# design.net
KiCad netlist of a schematic drawn in Altium Designer
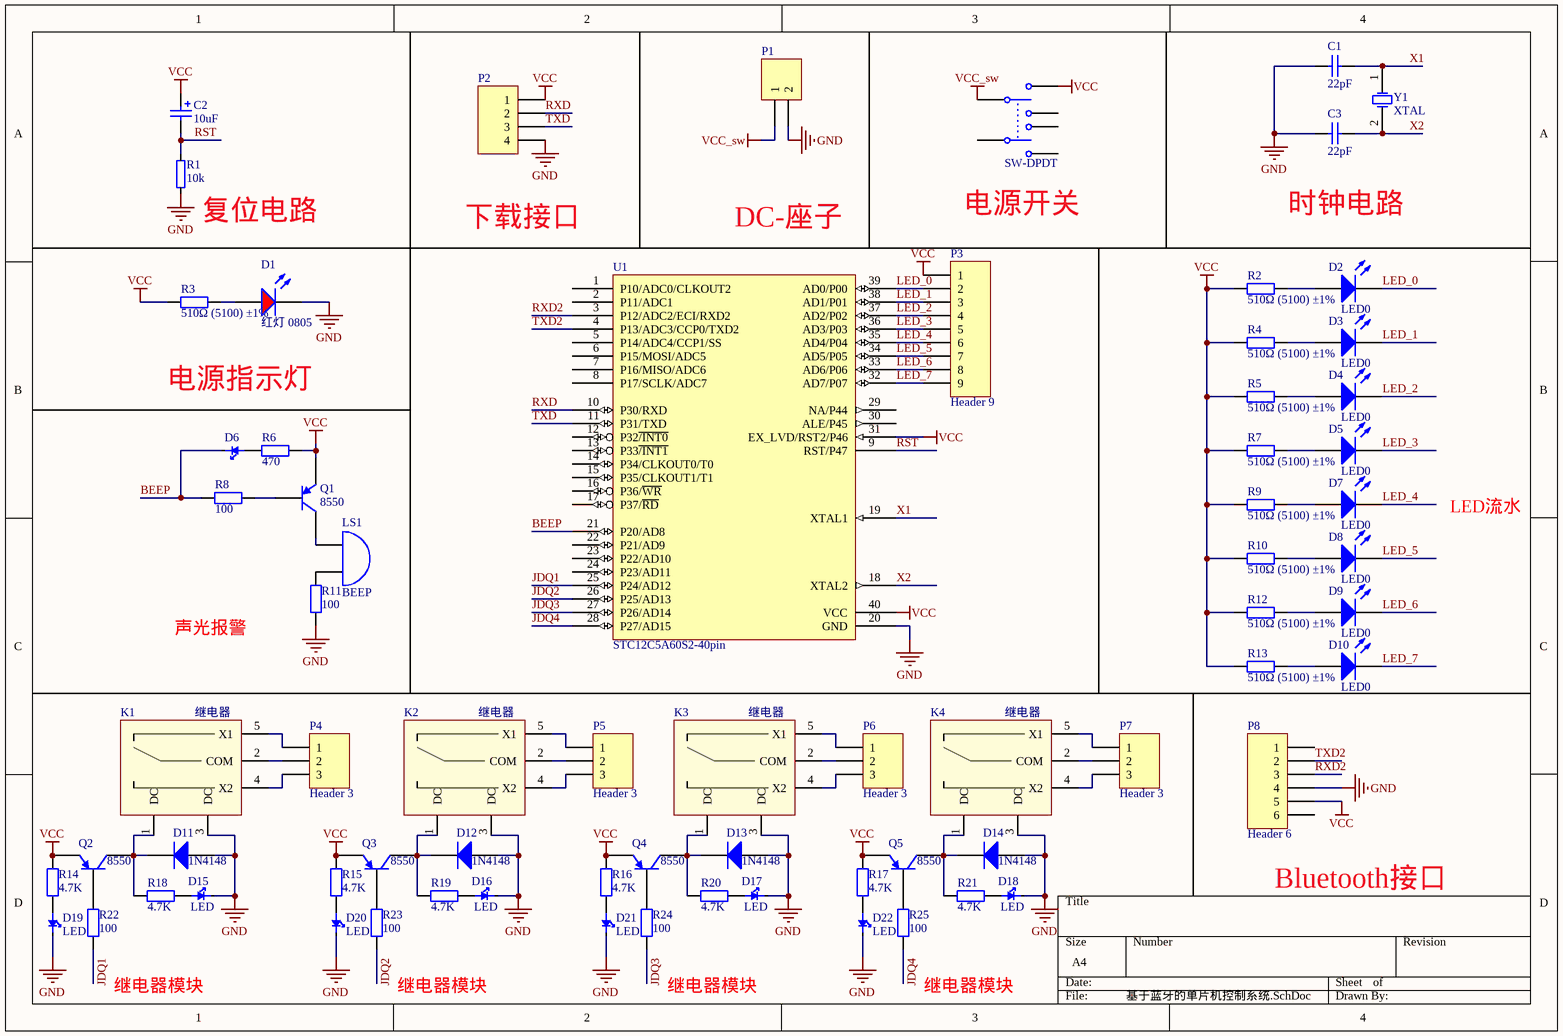
[diagram p0: 基于蓝牙的单片机控制系统.SchDoc]

(export (version "E")
  (design (tool "Eeschema 10.0.6"))
  (components
    (comp (ref "C1")
      (value "22pF")
      (footprint "0805")
      (description "Capacitor")
      (fields (field (name "Comment") "Cap") (field (name "PUBLISHER") "Altium Limited"))
      (libsource (lib "Miscellaneous Devices") (part "Cap"))
    )
    (comp (ref "C2")
      (value "10uF")
      (footprint "RB.2/.5mm")
      (description "Polarized Capacitor (Axial)")
      (fields (field (name "PUBLISHER") "Altium Limited"))
      (libsource (lib "Miscellaneous Devices") (part "Cap Pol2"))
    )
    (comp (ref "C3")
      (value "22pF")
      (footprint "0805")
      (description "Capacitor")
      (fields (field (name "Comment") "Cap") (field (name "PUBLISHER") "Altium Limited"))
      (libsource (lib "Miscellaneous Devices") (part "Cap"))
    )
    (comp (ref "D1")
      (value "红灯 0805")
      (footprint "LC-0805_LED_S1")
      (description "发光二极管")
      (libsource (lib "Miscellaneous Devices LC") (part "0805 红灯"))
    )
    (comp (ref "D2")
      (value "LED0")
      (footprint "HDR1X2")
      (description "Typical INFRARED GaAs LED")
      (fields (field (name "PUBLISHER") "Altium Limited"))
      (libsource (lib "Miscellaneous Devices") (part "LED0"))
    )
    (comp (ref "D3")
      (value "LED0")
      (footprint "HDR1X2")
      (description "Typical INFRARED GaAs LED")
      (fields (field (name "PUBLISHER") "Altium Limited"))
      (libsource (lib "Miscellaneous Devices") (part "LED0"))
    )
    (comp (ref "D4")
      (value "LED0")
      (footprint "HDR1X2")
      (description "Typical INFRARED GaAs LED")
      (fields (field (name "PUBLISHER") "Altium Limited"))
      (libsource (lib "Miscellaneous Devices") (part "LED0"))
    )
    (comp (ref "D5")
      (value "LED0")
      (footprint "HDR1X2")
      (description "Typical INFRARED GaAs LED")
      (fields (field (name "PUBLISHER") "Altium Limited"))
      (libsource (lib "Miscellaneous Devices") (part "LED0"))
    )
    (comp (ref "D6") (value "W") (footprint "LC-0805_LED_S1") (libsource (lib "个人") (part "LED")))
    (comp (ref "D7")
      (value "LED0")
      (footprint "HDR1X2")
      (description "Typical INFRARED GaAs LED")
      (fields (field (name "PUBLISHER") "Altium Limited"))
      (libsource (lib "Miscellaneous Devices") (part "LED0"))
    )
    (comp (ref "D8")
      (value "LED0")
      (footprint "HDR1X2")
      (description "Typical INFRARED GaAs LED")
      (fields (field (name "PUBLISHER") "Altium Limited"))
      (libsource (lib "Miscellaneous Devices") (part "LED0"))
    )
    (comp (ref "D9")
      (value "LED0")
      (footprint "HDR1X2")
      (description "Typical INFRARED GaAs LED")
      (fields (field (name "PUBLISHER") "Altium Limited"))
      (libsource (lib "Miscellaneous Devices") (part "LED0"))
    )
    (comp (ref "D10")
      (value "LED0")
      (footprint "HDR1X2")
      (description "Typical INFRARED GaAs LED")
      (fields (field (name "PUBLISHER") "Altium Limited"))
      (libsource (lib "Miscellaneous Devices") (part "LED0"))
    )
    (comp (ref "D11")
      (value "1N4148")
      (footprint "SMA(DO-214AC)_S5")
      (description "High Conductance Fast Diode")
      (fields (field (name "PUBLISHER") "Altium Limited"))
      (libsource (lib "Miscellaneous Devices") (part "Diode 1N4148"))
    )
    (comp (ref "D12")
      (value "1N4148")
      (footprint "SMA(DO-214AC)_S5")
      (description "High Conductance Fast Diode")
      (fields (field (name "PUBLISHER") "Altium Limited"))
      (libsource (lib "Miscellaneous Devices") (part "Diode 1N4148"))
    )
    (comp (ref "D13")
      (value "1N4148")
      (footprint "SMA(DO-214AC)_S5")
      (description "High Conductance Fast Diode")
      (fields (field (name "PUBLISHER") "Altium Limited"))
      (libsource (lib "Miscellaneous Devices") (part "Diode 1N4148"))
    )
    (comp (ref "D14")
      (value "1N4148")
      (footprint "SMA(DO-214AC)_S5")
      (description "High Conductance Fast Diode")
      (fields (field (name "PUBLISHER") "Altium Limited"))
      (libsource (lib "Miscellaneous Devices") (part "Diode 1N4148"))
    )
    (comp (ref "D15") (value "LED") (footprint "LC-0805_LED_S1") (libsource (lib "个人") (part "LED")))
    (comp (ref "D16") (value "LED") (footprint "LC-0805_LED_S1") (libsource (lib "个人") (part "LED")))
    (comp (ref "D17") (value "LED") (footprint "LC-0805_LED_S1") (libsource (lib "个人") (part "LED")))
    (comp (ref "D18") (value "LED") (footprint "LC-0805_LED_S1") (libsource (lib "个人") (part "LED")))
    (comp (ref "D19") (value "LED") (footprint "LC-0805_LED_S1") (libsource (lib "个人") (part "LED")))
    (comp (ref "D20") (value "LED") (footprint "LC-0805_LED_S1") (libsource (lib "个人") (part "LED")))
    (comp (ref "D21") (value "LED") (footprint "LC-0805_LED_S1") (libsource (lib "个人") (part "LED")))
    (comp (ref "D22") (value "LED") (footprint "LC-0805_LED_S1") (libsource (lib "个人") (part "LED")))
    (comp (ref "K1") (value "继电器") (footprint "继电器5PIN_切换") (libsource (lib "个人") (part "松乐继电器5V-5PIN")))
    (comp (ref "K2") (value "继电器") (footprint "继电器5PIN_切换") (libsource (lib "个人") (part "松乐继电器5V-5PIN")))
    (comp (ref "K3") (value "继电器") (footprint "继电器5PIN_切换") (libsource (lib "个人") (part "松乐继电器5V-5PIN")))
    (comp (ref "K4") (value "继电器") (footprint "继电器5PIN_切换") (libsource (lib "个人") (part "松乐继电器5V-5PIN")))
    (comp (ref "LS1")
      (value "BEEP")
      (footprint "PIN2")
      (description "Electrical Bell")
      (fields (field (name "PUBLISHER") "Altium Limited"))
      (libsource (lib "Miscellaneous Devices") (part "Bell"))
    )
    (comp (ref "P1")
      (value "电源")
      (footprint "DC插座")
      (description "Header, 2-Pin")
      (fields (field (name "PUBLISHER") "Altium Limited"))
      (libsource (lib "Miscellaneous Connectors") (part "Header 2"))
    )
    (comp (ref "P2")
      (value "下载口")
      (footprint "HDR1X4")
      (description "Header, 4-Pin")
      (fields (field (name "PUBLISHER") "Altium Limited"))
      (libsource (lib "Miscellaneous Connectors") (part "Header 4"))
    )
    (comp (ref "P3")
      (value "Header 9")
      (footprint "HDR1X9")
      (description "Header, 9-Pin")
      (fields (field (name "PUBLISHER") "Altium Limited"))
      (libsource (lib "Miscellaneous Connectors") (part "Header 9"))
    )
    (comp (ref "P4")
      (value "Header 3")
      (footprint "KF128-5_3")
      (description "Header, 3-Pin")
      (fields (field (name "PUBLISHER") "Altium Limited"))
      (libsource (lib "Miscellaneous Connectors") (part "Header 3"))
    )
    (comp (ref "P5")
      (value "Header 3")
      (footprint "KF128-5_3")
      (description "Header, 3-Pin")
      (fields (field (name "PUBLISHER") "Altium Limited"))
      (libsource (lib "Miscellaneous Connectors") (part "Header 3"))
    )
    (comp (ref "P6")
      (value "Header 3")
      (footprint "KF128-5_3")
      (description "Header, 3-Pin")
      (fields (field (name "PUBLISHER") "Altium Limited"))
      (libsource (lib "Miscellaneous Connectors") (part "Header 3"))
    )
    (comp (ref "P7")
      (value "Header 3")
      (footprint "KF128-5_3")
      (description "Header, 3-Pin")
      (fields (field (name "PUBLISHER") "Altium Limited"))
      (libsource (lib "Miscellaneous Connectors") (part "Header 3"))
    )
    (comp (ref "P8")
      (value "Header 6")
      (footprint "HDR1X6")
      (description "Header, 6-Pin")
      (fields (field (name "PUBLISHER") "Altium Limited"))
      (libsource (lib "Miscellaneous Connectors") (part "Header 6"))
    )
    (comp (ref "Q1")
      (value "8550")
      (footprint "SOT-23 MOS")
      (description "PNP General Purpose Amplifier")
      (fields (field (name "PUBLISHER") "Altium Limited"))
      (libsource (lib "Miscellaneous Devices") (part "2N3906"))
    )
    (comp (ref "Q2")
      (value "8550")
      (footprint "SOT-23 MOS")
      (description "PNP General Purpose Amplifier")
      (fields (field (name "PUBLISHER") "Altium Limited"))
      (libsource (lib "Miscellaneous Devices") (part "2N3906"))
    )
    (comp (ref "Q3")
      (value "8550")
      (footprint "SOT-23 MOS")
      (description "PNP General Purpose Amplifier")
      (fields (field (name "PUBLISHER") "Altium Limited"))
      (libsource (lib "Miscellaneous Devices") (part "2N3906"))
    )
    (comp (ref "Q4")
      (value "8550")
      (footprint "SOT-23 MOS")
      (description "PNP General Purpose Amplifier")
      (fields (field (name "PUBLISHER") "Altium Limited"))
      (libsource (lib "Miscellaneous Devices") (part "2N3906"))
    )
    (comp (ref "Q5")
      (value "8550")
      (footprint "SOT-23 MOS")
      (description "PNP General Purpose Amplifier")
      (fields (field (name "PUBLISHER") "Altium Limited"))
      (libsource (lib "Miscellaneous Devices") (part "2N3906"))
    )
    (comp (ref "R1") (value "10k") (footprint "0805") (libsource (lib "SCHS") (part "RES5")))
    (comp (ref "R2")
      (value "510Ω (5100) ±1%")
      (footprint "LC-0805_R")
      (description "贴片电阻")
      (libsource (lib "Miscellaneous Devices LC") (part "0805 510Ω (5100) 1%"))
    )
    (comp (ref "R3")
      (value "510Ω (5100) ±1%")
      (footprint "LC-0805_R")
      (description "贴片电阻")
      (libsource (lib "Miscellaneous Devices LC") (part "0805 510Ω (5100) 1%"))
    )
    (comp (ref "R4")
      (value "510Ω (5100) ±1%")
      (footprint "LC-0805_R")
      (description "贴片电阻")
      (libsource (lib "Miscellaneous Devices LC") (part "0805 510Ω (5100) 1%"))
    )
    (comp (ref "R5")
      (value "510Ω (5100) ±1%")
      (footprint "LC-0805_R")
      (description "贴片电阻")
      (libsource (lib "Miscellaneous Devices LC") (part "0805 510Ω (5100) 1%"))
    )
    (comp (ref "R6")
      (value "470")
      (footprint "0805")
      (description "Resistor")
      (fields (field (name "Comment") "Res2") (field (name "PUBLISHER") "Altium Limited"))
      (libsource (lib "") (part "Res2_2"))
    )
    (comp (ref "R7")
      (value "510Ω (5100) ±1%")
      (footprint "LC-0805_R")
      (description "贴片电阻")
      (libsource (lib "Miscellaneous Devices LC") (part "0805 510Ω (5100) 1%"))
    )
    (comp (ref "R8")
      (value "100")
      (footprint "0805")
      (description "Resistor")
      (fields (field (name "Comment") "Res2") (field (name "PUBLISHER") "Altium Limited"))
      (libsource (lib "") (part "Res2_2"))
    )
    (comp (ref "R9")
      (value "510Ω (5100) ±1%")
      (footprint "LC-0805_R")
      (description "贴片电阻")
      (libsource (lib "Miscellaneous Devices LC") (part "0805 510Ω (5100) 1%"))
    )
    (comp (ref "R10")
      (value "510Ω (5100) ±1%")
      (footprint "LC-0805_R")
      (description "贴片电阻")
      (libsource (lib "Miscellaneous Devices LC") (part "0805 510Ω (5100) 1%"))
    )
    (comp (ref "R11")
      (value "100")
      (footprint "0805")
      (description "Resistor")
      (fields (field (name "Comment") "Res2") (field (name "PUBLISHER") "Altium Limited"))
      (libsource (lib "Miscellaneous Devices") (part "Res2"))
    )
    (comp (ref "R12")
      (value "510Ω (5100) ±1%")
      (footprint "LC-0805_R")
      (description "贴片电阻")
      (libsource (lib "Miscellaneous Devices LC") (part "0805 510Ω (5100) 1%"))
    )
    (comp (ref "R13")
      (value "510Ω (5100) ±1%")
      (footprint "LC-0805_R")
      (description "贴片电阻")
      (libsource (lib "Miscellaneous Devices LC") (part "0805 510Ω (5100) 1%"))
    )
    (comp (ref "R14")
      (value "4.7K")
      (footprint "0805")
      (description "Resistor")
      (fields (field (name "PUBLISHER") "Altium Limited"))
      (libsource (lib "") (part "Res2_2"))
    )
    (comp (ref "R15")
      (value "4.7K")
      (footprint "0805")
      (description "Resistor")
      (fields (field (name "PUBLISHER") "Altium Limited"))
      (libsource (lib "") (part "Res2_2"))
    )
    (comp (ref "R16")
      (value "4.7K")
      (footprint "0805")
      (description "Resistor")
      (fields (field (name "PUBLISHER") "Altium Limited"))
      (libsource (lib "") (part "Res2_2"))
    )
    (comp (ref "R17")
      (value "4.7K")
      (footprint "0805")
      (description "Resistor")
      (fields (field (name "PUBLISHER") "Altium Limited"))
      (libsource (lib "") (part "Res2_2"))
    )
    (comp (ref "R18")
      (value "4.7K")
      (footprint "0805")
      (description "Resistor")
      (fields (field (name "PUBLISHER") "Altium Limited"))
      (libsource (lib "") (part "Res2_1"))
    )
    (comp (ref "R19")
      (value "4.7K")
      (footprint "0805")
      (description "Resistor")
      (fields (field (name "PUBLISHER") "Altium Limited"))
      (libsource (lib "") (part "Res2_1"))
    )
    (comp (ref "R20")
      (value "4.7K")
      (footprint "0805")
      (description "Resistor")
      (fields (field (name "PUBLISHER") "Altium Limited"))
      (libsource (lib "") (part "Res2_1"))
    )
    (comp (ref "R21")
      (value "4.7K")
      (footprint "0805")
      (description "Resistor")
      (fields (field (name "PUBLISHER") "Altium Limited"))
      (libsource (lib "") (part "Res2_1"))
    )
    (comp (ref "R22")
      (value "100")
      (footprint "0805")
      (description "Resistor")
      (fields (field (name "PUBLISHER") "Altium Limited"))
      (libsource (lib "Miscellaneous Devices") (part "Res2"))
    )
    (comp (ref "R23")
      (value "100")
      (footprint "0805")
      (description "Resistor")
      (fields (field (name "PUBLISHER") "Altium Limited"))
      (libsource (lib "Miscellaneous Devices") (part "Res2"))
    )
    (comp (ref "R24")
      (value "100")
      (footprint "0805")
      (description "Resistor")
      (fields (field (name "PUBLISHER") "Altium Limited"))
      (libsource (lib "Miscellaneous Devices") (part "Res2"))
    )
    (comp (ref "R25")
      (value "100")
      (footprint "0805")
      (description "Resistor")
      (fields (field (name "PUBLISHER") "Altium Limited"))
      (libsource (lib "Miscellaneous Devices") (part "Res2"))
    )
    (comp (ref "U1")
      (value "STC12C5A60S2-40pin")
      (footprint "DIP40")
      (libsource (lib "个人") (part "STC12C5A60S2-40pin"))
    )
    (comp (ref "Y1")
      (value "XTAL")
      (footprint "XTAL")
      (description "Crystal Oscillator")
      (fields (field (name "PUBLISHER") "Altium Limited"))
      (libsource (lib "Miscellaneous Devices") (part "XTAL"))
    )
    (comp (ref "常按开关1")
      (value "SW-DPDT")
      (footprint "DPDT-6")
      (description "Double-Pole, Double-Throw Switch")
      (fields (field (name "PUBLISHER") "Altium Limited"))
      (libsource (lib "Miscellaneous Devices") (part "SW-DPDT"))
    )
  )
  (nets
    (net (code "1") (name "/BEEP") (class "Default")
      (node (ref "D6") (pin "K") (pinfunction "K_K") (pintype "passive"))
      (node (ref "R8") (pin "2") (pinfunction "2_2") (pintype "passive"))
      (node (ref "U1") (pin "21") (pinfunction "P20/AD8_21") (pintype "bidirectional"))
    )
    (net (code "2") (name "/JDQ1") (class "Default")
      (node (ref "R22") (pin "1") (pinfunction "1_1") (pintype "passive"))
      (node (ref "U1") (pin "25") (pinfunction "P24/AD12_25") (pintype "bidirectional"))
    )
    (net (code "3") (name "/JDQ2") (class "Default")
      (node (ref "R23") (pin "1") (pinfunction "1_1") (pintype "passive"))
      (node (ref "U1") (pin "26") (pinfunction "P25/AD13_26") (pintype "bidirectional"))
    )
    (net (code "4") (name "/JDQ3") (class "Default")
      (node (ref "R24") (pin "1") (pinfunction "1_1") (pintype "passive"))
      (node (ref "U1") (pin "27") (pinfunction "P26/AD14_27") (pintype "bidirectional"))
    )
    (net (code "5") (name "/JDQ4") (class "Default")
      (node (ref "R25") (pin "1") (pinfunction "1_1") (pintype "passive"))
      (node (ref "U1") (pin "28") (pinfunction "P27/AD15_28") (pintype "bidirectional"))
    )
    (net (code "6") (name "/LED_0") (class "Default")
      (node (ref "D2") (pin "2") (pinfunction "K_2") (pintype "passive"))
      (node (ref "P3") (pin "2") (pinfunction "2_2") (pintype "passive"))
      (node (ref "U1") (pin "39") (pinfunction "AD0/P00_39") (pintype "bidirectional"))
    )
    (net (code "7") (name "/LED_1") (class "Default")
      (node (ref "D3") (pin "2") (pinfunction "K_2") (pintype "passive"))
      (node (ref "P3") (pin "3") (pinfunction "3_3") (pintype "passive"))
      (node (ref "U1") (pin "38") (pinfunction "AD1/P01_38") (pintype "bidirectional"))
    )
    (net (code "8") (name "/LED_2") (class "Default")
      (node (ref "D4") (pin "2") (pinfunction "K_2") (pintype "passive"))
      (node (ref "P3") (pin "4") (pinfunction "4_4") (pintype "passive"))
      (node (ref "U1") (pin "37") (pinfunction "AD2/P02_37") (pintype "bidirectional"))
    )
    (net (code "9") (name "/LED_3") (class "Default")
      (node (ref "D5") (pin "2") (pinfunction "K_2") (pintype "passive"))
      (node (ref "P3") (pin "5") (pinfunction "5_5") (pintype "passive"))
      (node (ref "U1") (pin "36") (pinfunction "AD3/P03_36") (pintype "bidirectional"))
    )
    (net (code "10") (name "/LED_4") (class "Default")
      (node (ref "D7") (pin "2") (pinfunction "K_2") (pintype "passive"))
      (node (ref "P3") (pin "6") (pinfunction "6_6") (pintype "passive"))
      (node (ref "U1") (pin "35") (pinfunction "AD4/P04_35") (pintype "bidirectional"))
    )
    (net (code "11") (name "/LED_5") (class "Default")
      (node (ref "D8") (pin "2") (pinfunction "K_2") (pintype "passive"))
      (node (ref "P3") (pin "7") (pinfunction "7_7") (pintype "passive"))
      (node (ref "U1") (pin "34") (pinfunction "AD5/P05_34") (pintype "bidirectional"))
    )
    (net (code "12") (name "/LED_6") (class "Default")
      (node (ref "D9") (pin "2") (pinfunction "K_2") (pintype "passive"))
      (node (ref "P3") (pin "8") (pinfunction "8_8") (pintype "passive"))
      (node (ref "U1") (pin "33") (pinfunction "AD6/P06_33") (pintype "bidirectional"))
    )
    (net (code "13") (name "/LED_7") (class "Default")
      (node (ref "D10") (pin "2") (pinfunction "K_2") (pintype "passive"))
      (node (ref "P3") (pin "9") (pinfunction "9_9") (pintype "passive"))
      (node (ref "U1") (pin "32") (pinfunction "AD7/P07_32") (pintype "bidirectional"))
    )
    (net (code "14") (name "/RST") (class "Default")
      (node (ref "C2") (pin "2") (pinfunction "2_2") (pintype "passive"))
      (node (ref "R1") (pin "2") (pintype "passive"))
      (node (ref "U1") (pin "9") (pinfunction "RST/P47_9") (pintype "passive"))
    )
    (net (code "15") (name "/RXD") (class "Default")
      (node (ref "P2") (pin "2") (pinfunction "2_2") (pintype "passive"))
      (node (ref "U1") (pin "10") (pinfunction "P30/RXD_10") (pintype "bidirectional"))
    )
    (net (code "16") (name "/RXD2") (class "Default")
      (node (ref "P8") (pin "3") (pinfunction "3_3") (pintype "passive"))
      (node (ref "U1") (pin "3") (pinfunction "P12/ADC2/ECI/RXD2_3") (pintype "passive"))
    )
    (net (code "17") (name "/TXD") (class "Default")
      (node (ref "P2") (pin "3") (pinfunction "3_3") (pintype "passive"))
      (node (ref "U1") (pin "11") (pinfunction "P31/TXD_11") (pintype "bidirectional"))
    )
    (net (code "18") (name "/TXD2") (class "Default")
      (node (ref "P8") (pin "2") (pinfunction "2_2") (pintype "passive"))
      (node (ref "U1") (pin "4") (pinfunction "P13/ADC3/CCP0/TXD2_4") (pintype "passive"))
    )
    (net (code "19") (name "/X1") (class "Default")
      (node (ref "C1") (pin "2") (pinfunction "2_2") (pintype "passive"))
      (node (ref "U1") (pin "19") (pinfunction "XTAL1_19") (pintype "input"))
      (node (ref "Y1") (pin "1") (pinfunction "OSC1_1") (pintype "passive"))
    )
    (net (code "20") (name "/X2") (class "Default")
      (node (ref "C3") (pin "2") (pinfunction "2_2") (pintype "passive"))
      (node (ref "U1") (pin "18") (pinfunction "XTAL2_18") (pintype "output"))
      (node (ref "Y1") (pin "2") (pinfunction "OSC2_2") (pintype "passive"))
    )
    (net (code "21") (name "GND") (class "Default")
      (node (ref "C1") (pin "1") (pinfunction "1_1") (pintype "passive"))
      (node (ref "C3") (pin "1") (pinfunction "1_1") (pintype "passive"))
      (node (ref "D1") (pin "K") (pinfunction "K_K") (pintype "passive"))
      (node (ref "D11") (pin "1") (pinfunction "A_1") (pintype "passive"))
      (node (ref "D12") (pin "1") (pinfunction "A_1") (pintype "passive"))
      (node (ref "D13") (pin "1") (pinfunction "A_1") (pintype "passive"))
      (node (ref "D14") (pin "1") (pinfunction "A_1") (pintype "passive"))
      (node (ref "D15") (pin "K") (pinfunction "K_K") (pintype "passive"))
      (node (ref "D16") (pin "K") (pinfunction "K_K") (pintype "passive"))
      (node (ref "D17") (pin "K") (pinfunction "K_K") (pintype "passive"))
      (node (ref "D18") (pin "K") (pinfunction "K_K") (pintype "passive"))
      (node (ref "D19") (pin "K") (pinfunction "K_K") (pintype "passive"))
      (node (ref "D20") (pin "K") (pinfunction "K_K") (pintype "passive"))
      (node (ref "D21") (pin "K") (pinfunction "K_K") (pintype "passive"))
      (node (ref "D22") (pin "K") (pinfunction "K_K") (pintype "passive"))
      (node (ref "K1") (pin "3") (pinfunction "DC_3") (pintype "passive"))
      (node (ref "K2") (pin "3") (pinfunction "DC_3") (pintype "passive"))
      (node (ref "K3") (pin "3") (pinfunction "DC_3") (pintype "passive"))
      (node (ref "K4") (pin "3") (pinfunction "DC_3") (pintype "passive"))
      (node (ref "P1") (pin "2") (pinfunction "2_2") (pintype "passive"))
      (node (ref "P2") (pin "4") (pinfunction "4_4") (pintype "passive"))
      (node (ref "P8") (pin "4") (pinfunction "4_4") (pintype "passive"))
      (node (ref "R1") (pin "1") (pintype "passive"))
      (node (ref "R11") (pin "1") (pinfunction "1_1") (pintype "passive"))
      (node (ref "U1") (pin "20") (pinfunction "GND_20") (pintype "power_in"))
    )
    (net (code "22") (name "Net-(D1-PadA)") (class "Default")
      (node (ref "D1") (pin "A") (pinfunction "A_A") (pintype "passive"))
      (node (ref "R3") (pin "2") (pinfunction "2_2") (pintype "passive"))
    )
    (net (code "23") (name "Net-(D2-A)") (class "Default")
      (node (ref "D2") (pin "1") (pinfunction "A_1") (pintype "passive"))
      (node (ref "R2") (pin "2") (pinfunction "2_2") (pintype "passive"))
    )
    (net (code "24") (name "Net-(D3-A)") (class "Default")
      (node (ref "D3") (pin "1") (pinfunction "A_1") (pintype "passive"))
      (node (ref "R4") (pin "2") (pinfunction "2_2") (pintype "passive"))
    )
    (net (code "25") (name "Net-(D4-A)") (class "Default")
      (node (ref "D4") (pin "1") (pinfunction "A_1") (pintype "passive"))
      (node (ref "R5") (pin "2") (pinfunction "2_2") (pintype "passive"))
    )
    (net (code "26") (name "Net-(D5-A)") (class "Default")
      (node (ref "D5") (pin "1") (pinfunction "A_1") (pintype "passive"))
      (node (ref "R7") (pin "2") (pinfunction "2_2") (pintype "passive"))
    )
    (net (code "27") (name "Net-(D6-PadA)") (class "Default")
      (node (ref "D6") (pin "A") (pinfunction "A_A") (pintype "passive"))
      (node (ref "R6") (pin "2") (pinfunction "2_2") (pintype "passive"))
    )
    (net (code "28") (name "Net-(D7-A)") (class "Default")
      (node (ref "D7") (pin "1") (pinfunction "A_1") (pintype "passive"))
      (node (ref "R9") (pin "2") (pinfunction "2_2") (pintype "passive"))
    )
    (net (code "29") (name "Net-(D8-A)") (class "Default")
      (node (ref "D8") (pin "1") (pinfunction "A_1") (pintype "passive"))
      (node (ref "R10") (pin "2") (pinfunction "2_2") (pintype "passive"))
    )
    (net (code "30") (name "Net-(D9-A)") (class "Default")
      (node (ref "D9") (pin "1") (pinfunction "A_1") (pintype "passive"))
      (node (ref "R12") (pin "2") (pinfunction "2_2") (pintype "passive"))
    )
    (net (code "31") (name "Net-(D10-A)") (class "Default")
      (node (ref "D10") (pin "1") (pinfunction "A_1") (pintype "passive"))
      (node (ref "R13") (pin "2") (pinfunction "2_2") (pintype "passive"))
    )
    (net (code "32") (name "Net-(D11-K)") (class "Default")
      (node (ref "D11") (pin "2") (pinfunction "K_2") (pintype "passive"))
      (node (ref "K1") (pin "1") (pinfunction "DC_1") (pintype "passive"))
      (node (ref "Q2") (pin "3") (pinfunction "C_3") (pintype "passive"))
      (node (ref "R18") (pin "2") (pinfunction "2_2") (pintype "passive"))
    )
    (net (code "33") (name "Net-(D12-K)") (class "Default")
      (node (ref "D12") (pin "2") (pinfunction "K_2") (pintype "passive"))
      (node (ref "K2") (pin "1") (pinfunction "DC_1") (pintype "passive"))
      (node (ref "Q3") (pin "3") (pinfunction "C_3") (pintype "passive"))
      (node (ref "R19") (pin "2") (pinfunction "2_2") (pintype "passive"))
    )
    (net (code "34") (name "Net-(D13-K)") (class "Default")
      (node (ref "D13") (pin "2") (pinfunction "K_2") (pintype "passive"))
      (node (ref "K3") (pin "1") (pinfunction "DC_1") (pintype "passive"))
      (node (ref "Q4") (pin "3") (pinfunction "C_3") (pintype "passive"))
      (node (ref "R20") (pin "2") (pinfunction "2_2") (pintype "passive"))
    )
    (net (code "35") (name "Net-(D14-K)") (class "Default")
      (node (ref "D14") (pin "2") (pinfunction "K_2") (pintype "passive"))
      (node (ref "K4") (pin "1") (pinfunction "DC_1") (pintype "passive"))
      (node (ref "Q5") (pin "3") (pinfunction "C_3") (pintype "passive"))
      (node (ref "R21") (pin "2") (pinfunction "2_2") (pintype "passive"))
    )
    (net (code "36") (name "Net-(D15-PadA)") (class "Default")
      (node (ref "D15") (pin "A") (pinfunction "A_A") (pintype "passive"))
      (node (ref "R18") (pin "1") (pinfunction "1_1") (pintype "passive"))
    )
    (net (code "37") (name "Net-(D16-PadA)") (class "Default")
      (node (ref "D16") (pin "A") (pinfunction "A_A") (pintype "passive"))
      (node (ref "R19") (pin "1") (pinfunction "1_1") (pintype "passive"))
    )
    (net (code "38") (name "Net-(D17-PadA)") (class "Default")
      (node (ref "D17") (pin "A") (pinfunction "A_A") (pintype "passive"))
      (node (ref "R20") (pin "1") (pinfunction "1_1") (pintype "passive"))
    )
    (net (code "39") (name "Net-(D18-PadA)") (class "Default")
      (node (ref "D18") (pin "A") (pinfunction "A_A") (pintype "passive"))
      (node (ref "R21") (pin "1") (pinfunction "1_1") (pintype "passive"))
    )
    (net (code "40") (name "Net-(D19-PadA)") (class "Default")
      (node (ref "D19") (pin "A") (pinfunction "A_A") (pintype "passive"))
      (node (ref "R14") (pin "2") (pinfunction "2_2") (pintype "passive"))
    )
    (net (code "41") (name "Net-(D20-PadA)") (class "Default")
      (node (ref "D20") (pin "A") (pinfunction "A_A") (pintype "passive"))
      (node (ref "R15") (pin "2") (pinfunction "2_2") (pintype "passive"))
    )
    (net (code "42") (name "Net-(D21-PadA)") (class "Default")
      (node (ref "D21") (pin "A") (pinfunction "A_A") (pintype "passive"))
      (node (ref "R16") (pin "2") (pinfunction "2_2") (pintype "passive"))
    )
    (net (code "43") (name "Net-(D22-PadA)") (class "Default")
      (node (ref "D22") (pin "A") (pinfunction "A_A") (pintype "passive"))
      (node (ref "R17") (pin "2") (pinfunction "2_2") (pintype "passive"))
    )
    (net (code "44") (name "Net-(K1-COM)") (class "Default")
      (node (ref "K1") (pin "2") (pinfunction "COM_2") (pintype "passive"))
      (node (ref "P4") (pin "2") (pinfunction "2_2") (pintype "passive"))
    )
    (net (code "45") (name "Net-(K1-X1)") (class "Default")
      (node (ref "K1") (pin "5") (pinfunction "X1_5") (pintype "passive"))
      (node (ref "P4") (pin "1") (pinfunction "1_1") (pintype "passive"))
    )
    (net (code "46") (name "Net-(K1-X2)") (class "Default")
      (node (ref "K1") (pin "4") (pinfunction "X2_4") (pintype "passive"))
      (node (ref "P4") (pin "3") (pinfunction "3_3") (pintype "passive"))
    )
    (net (code "47") (name "Net-(K2-COM)") (class "Default")
      (node (ref "K2") (pin "2") (pinfunction "COM_2") (pintype "passive"))
      (node (ref "P5") (pin "2") (pinfunction "2_2") (pintype "passive"))
    )
    (net (code "48") (name "Net-(K2-X1)") (class "Default")
      (node (ref "K2") (pin "5") (pinfunction "X1_5") (pintype "passive"))
      (node (ref "P5") (pin "1") (pinfunction "1_1") (pintype "passive"))
    )
    (net (code "49") (name "Net-(K2-X2)") (class "Default")
      (node (ref "K2") (pin "4") (pinfunction "X2_4") (pintype "passive"))
      (node (ref "P5") (pin "3") (pinfunction "3_3") (pintype "passive"))
    )
    (net (code "50") (name "Net-(K3-COM)") (class "Default")
      (node (ref "K3") (pin "2") (pinfunction "COM_2") (pintype "passive"))
      (node (ref "P6") (pin "2") (pinfunction "2_2") (pintype "passive"))
    )
    (net (code "51") (name "Net-(K3-X1)") (class "Default")
      (node (ref "K3") (pin "5") (pinfunction "X1_5") (pintype "passive"))
      (node (ref "P6") (pin "1") (pinfunction "1_1") (pintype "passive"))
    )
    (net (code "52") (name "Net-(K3-X2)") (class "Default")
      (node (ref "K3") (pin "4") (pinfunction "X2_4") (pintype "passive"))
      (node (ref "P6") (pin "3") (pinfunction "3_3") (pintype "passive"))
    )
    (net (code "53") (name "Net-(K4-COM)") (class "Default")
      (node (ref "K4") (pin "2") (pinfunction "COM_2") (pintype "passive"))
      (node (ref "P7") (pin "2") (pinfunction "2_2") (pintype "passive"))
    )
    (net (code "54") (name "Net-(K4-X1)") (class "Default")
      (node (ref "K4") (pin "5") (pinfunction "X1_5") (pintype "passive"))
      (node (ref "P7") (pin "1") (pinfunction "1_1") (pintype "passive"))
    )
    (net (code "55") (name "Net-(K4-X2)") (class "Default")
      (node (ref "K4") (pin "4") (pinfunction "X2_4") (pintype "passive"))
      (node (ref "P7") (pin "3") (pinfunction "3_3") (pintype "passive"))
    )
    (net (code "56") (name "Net-(LS1-A)") (class "Default")
      (node (ref "LS1") (pin "1") (pinfunction "A_1") (pintype "passive"))
      (node (ref "Q1") (pin "3") (pinfunction "C_3") (pintype "passive"))
    )
    (net (code "57") (name "Net-(LS1-B)") (class "Default")
      (node (ref "LS1") (pin "2") (pinfunction "B_2") (pintype "passive"))
      (node (ref "R11") (pin "2") (pinfunction "2_2") (pintype "passive"))
    )
    (net (code "58") (name "Net-(Q1-B)") (class "Default")
      (node (ref "Q1") (pin "2") (pinfunction "B_2") (pintype "passive"))
      (node (ref "R8") (pin "1") (pinfunction "1_1") (pintype "passive"))
    )
    (net (code "59") (name "Net-(Q2-B)") (class "Default")
      (node (ref "Q2") (pin "2") (pinfunction "B_2") (pintype "passive"))
      (node (ref "R22") (pin "2") (pinfunction "2_2") (pintype "passive"))
    )
    (net (code "60") (name "Net-(Q3-B)") (class "Default")
      (node (ref "Q3") (pin "2") (pinfunction "B_2") (pintype "passive"))
      (node (ref "R23") (pin "2") (pinfunction "2_2") (pintype "passive"))
    )
    (net (code "61") (name "Net-(Q4-B)") (class "Default")
      (node (ref "Q4") (pin "2") (pinfunction "B_2") (pintype "passive"))
      (node (ref "R24") (pin "2") (pinfunction "2_2") (pintype "passive"))
    )
    (net (code "62") (name "Net-(Q5-B)") (class "Default")
      (node (ref "Q5") (pin "2") (pinfunction "B_2") (pintype "passive"))
      (node (ref "R25") (pin "2") (pinfunction "2_2") (pintype "passive"))
    )
    (net (code "63") (name "VCC") (class "Default")
      (node (ref "C2") (pin "1") (pinfunction "1_1") (pintype "passive"))
      (node (ref "P2") (pin "1") (pinfunction "1_1") (pintype "passive"))
      (node (ref "P3") (pin "1") (pinfunction "1_1") (pintype "passive"))
      (node (ref "P8") (pin "5") (pinfunction "5_5") (pintype "passive"))
      (node (ref "Q1") (pin "1") (pinfunction "E_1") (pintype "passive"))
      (node (ref "Q2") (pin "1") (pinfunction "E_1") (pintype "passive"))
      (node (ref "Q3") (pin "1") (pinfunction "E_1") (pintype "passive"))
      (node (ref "Q4") (pin "1") (pinfunction "E_1") (pintype "passive"))
      (node (ref "Q5") (pin "1") (pinfunction "E_1") (pintype "passive"))
      (node (ref "R10") (pin "1") (pinfunction "1_1") (pintype "passive"))
      (node (ref "R12") (pin "1") (pinfunction "1_1") (pintype "passive"))
      (node (ref "R13") (pin "1") (pinfunction "1_1") (pintype "passive"))
      (node (ref "R14") (pin "1") (pinfunction "1_1") (pintype "passive"))
      (node (ref "R15") (pin "1") (pinfunction "1_1") (pintype "passive"))
      (node (ref "R16") (pin "1") (pinfunction "1_1") (pintype "passive"))
      (node (ref "R17") (pin "1") (pinfunction "1_1") (pintype "passive"))
      (node (ref "R2") (pin "1") (pinfunction "1_1") (pintype "passive"))
      (node (ref "R3") (pin "1") (pinfunction "1_1") (pintype "passive"))
      (node (ref "R4") (pin "1") (pinfunction "1_1") (pintype "passive"))
      (node (ref "R5") (pin "1") (pinfunction "1_1") (pintype "passive"))
      (node (ref "R6") (pin "1") (pinfunction "1_1") (pintype "passive"))
      (node (ref "R7") (pin "1") (pinfunction "1_1") (pintype "passive"))
      (node (ref "R9") (pin "1") (pinfunction "1_1") (pintype "passive"))
      (node (ref "U1") (pin "31") (pinfunction "EX_LVD/RST2/P46_31") (pintype "input"))
      (node (ref "U1") (pin "40") (pinfunction "VCC_40") (pintype "passive"))
      (node (ref "常按开关1") (pin "2") (pinfunction "2_2") (pintype "passive"))
    )
    (net (code "64") (name "VCC_sw") (class "Default")
      (node (ref "P1") (pin "1") (pinfunction "1_1") (pintype "passive"))
      (node (ref "常按开关1") (pin "1") (pinfunction "1_1") (pintype "passive"))
    )
    (net (code "65") (name "unconnected-(P8-Pad1)") (class "Default")
      (node (ref "P8") (pin "1") (pinfunction "1_1") (pintype "passive"))
    )
    (net (code "66") (name "unconnected-(P8-Pad6)") (class "Default")
      (node (ref "P8") (pin "6") (pinfunction "6_6") (pintype "passive"))
    )
    (net (code "67") (name "unconnected-(U1-ALE{slash}P45-Pad30)") (class "Default")
      (node (ref "U1") (pin "30") (pinfunction "ALE/P45_30") (pintype "output"))
    )
    (net (code "68") (name "unconnected-(U1-NA{slash}P44-Pad29)") (class "Default")
      (node (ref "U1") (pin "29") (pinfunction "NA/P44_29") (pintype "output"))
    )
    (net (code "69") (name "unconnected-(U1-P10{slash}ADC0{slash}CLKOUT2-Pad1)") (class "Default")
      (node (ref "U1") (pin "1") (pinfunction "P10/ADC0/CLKOUT2_1") (pintype "passive"))
    )
    (net (code "70") (name "unconnected-(U1-P11{slash}ADC1-Pad2)") (class "Default")
      (node (ref "U1") (pin "2") (pinfunction "P11/ADC1_2") (pintype "passive"))
    )
    (net (code "71") (name "unconnected-(U1-P14{slash}ADC4{slash}CCP1{slash}SS-Pad5)") (class "Default")
      (node (ref "U1") (pin "5") (pinfunction "P14/ADC4/CCP1/SS_5") (pintype "passive"))
    )
    (net (code "72") (name "unconnected-(U1-P15{slash}MOSI{slash}ADC5-Pad6)") (class "Default")
      (node (ref "U1") (pin "6") (pinfunction "P15/MOSI/ADC5_6") (pintype "passive"))
    )
    (net (code "73") (name "unconnected-(U1-P16{slash}MISO{slash}ADC6-Pad7)") (class "Default")
      (node (ref "U1") (pin "7") (pinfunction "P16/MISO/ADC6_7") (pintype "passive"))
    )
    (net (code "74") (name "unconnected-(U1-P17{slash}SCLK{slash}ADC7-Pad8)") (class "Default")
      (node (ref "U1") (pin "8") (pinfunction "P17/SCLK/ADC7_8") (pintype "passive"))
    )
    (net (code "75") (name "unconnected-(U1-P21{slash}AD9-Pad22)") (class "Default")
      (node (ref "U1") (pin "22") (pinfunction "P21/AD9_22") (pintype "bidirectional"))
    )
    (net (code "76") (name "unconnected-(U1-P22{slash}AD10-Pad23)") (class "Default")
      (node (ref "U1") (pin "23") (pinfunction "P22/AD10_23") (pintype "bidirectional"))
    )
    (net (code "77") (name "unconnected-(U1-P23{slash}AD11-Pad24)") (class "Default")
      (node (ref "U1") (pin "24") (pinfunction "P23/AD11_24") (pintype "bidirectional"))
    )
    (net (code "78") (name "unconnected-(U1-P32~{{slash}INT0}-Pad12)") (class "Default")
      (node (ref "U1") (pin "12") (pinfunction "P32~{/INT0}_12") (pintype "bidirectional"))
    )
    (net (code "79") (name "unconnected-(U1-P33~{{slash}INT1}-Pad13)") (class "Default")
      (node (ref "U1") (pin "13") (pinfunction "P33~{/INT1}_13") (pintype "bidirectional"))
    )
    (net (code "80") (name "unconnected-(U1-P34{slash}CLKOUT0{slash}T0-Pad14)") (class "Default")
      (node (ref "U1") (pin "14") (pinfunction "P34/CLKOUT0/T0_14") (pintype "bidirectional"))
    )
    (net (code "81") (name "unconnected-(U1-P35{slash}CLKOUT1{slash}T1-Pad15)") (class "Default")
      (node (ref "U1") (pin "15") (pinfunction "P35/CLKOUT1/T1_15") (pintype "bidirectional"))
    )
    (net (code "82") (name "unconnected-(U1-P36{slash}~{WR}-Pad16)") (class "Default")
      (node (ref "U1") (pin "16") (pinfunction "P36/~{WR}_16") (pintype "bidirectional"))
    )
    (net (code "83") (name "unconnected-(U1-P37{slash}~{RD}-Pad17)") (class "Default")
      (node (ref "U1") (pin "17") (pinfunction "P37/~{RD}_17") (pintype "bidirectional"))
    )
    (net (code "84") (name "unconnected-(常按开关1-Pad3)") (class "Default")
      (node (ref "常按开关1") (pin "3") (pinfunction "3_3") (pintype "passive"))
    )
    (net (code "85") (name "unconnected-(常按开关1-Pad4)") (class "Default")
      (node (ref "常按开关1") (pin "4") (pinfunction "4_4") (pintype "passive"))
    )
    (net (code "86") (name "unconnected-(常按开关1-Pad5)") (class "Default")
      (node (ref "常按开关1") (pin "5") (pinfunction "5_5") (pintype "passive"))
    )
    (net (code "87") (name "unconnected-(常按开关1-Pad6)") (class "Default")
      (node (ref "常按开关1") (pin "6") (pinfunction "6_6") (pintype "passive"))
    )
  )
)
